# LEDBAKL_AP3036.net
KiCad netlist of a schematic drawn in Altium Designer
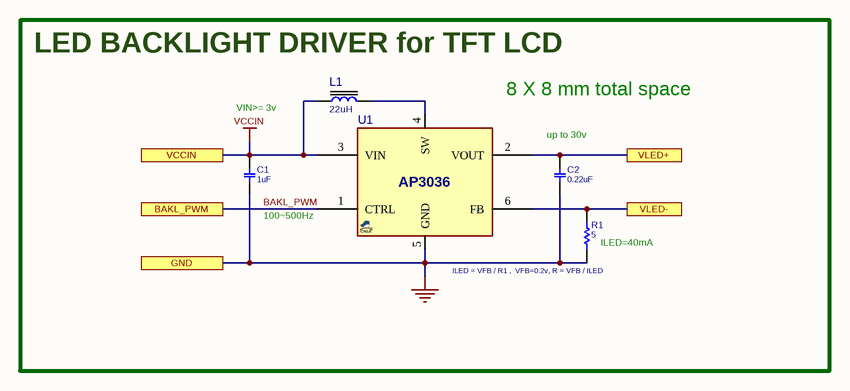
[diagram p0: LEDBAKL_AP3036.SchDoc]

(export (version "E")
  (design (tool "Eeschema 10.0.6"))
  (components
    (comp (ref "C1")
      (value "1uF")
      (footprint "C0603")
      (description "CAP, MLCC")
      (fields (field (name "MANF_P#") "CL10A105KB8NNNC") (field (name "MANF") "Samsung"))
      (libsource (lib "passive_smd") (part "CAP_SMD_MLCC"))
    )
    (comp (ref "C2")
      (value "0.22uF")
      (footprint "C0402")
      (description "CAP, MLCC")
      (libsource (lib "passive_smd") (part "CAP_SMD_MLCC"))
    )
    (comp (ref "L1")
      (value "22uH")
      (footprint "L_4")
      (description "INDUCTOR, POWER, SMD")
      (fields (field (name "MANF_P#") "CY43-22UH"))
      (libsource (lib "passive") (part "INDPWR_SMD"))
    )
    (comp (ref "R1")
      (value "5")
      (footprint "R0402")
      (description "RESISTOR, SMD, 20K, 0402")
      (fields (field (name "MANF") "Yageo") (field (name "MANF_P#") "RK73H1ETTP2002F"))
      (libsource (lib "chila_passive") (part "RES_SMD"))
    )
    (comp (ref "U1")
      (value "AP3036")
      (footprint "SOT23_6")
      (description "REG, Switching, Boost, 0.55A, ADJ, 1MHz, SOT-23-6")
      (fields (field (name "MANF_P#") "AP3036K, AP3036BK") (field (name "MANF") "Diodes"))
      (libsource (lib "pwr_switching_boost") (part "VREG_AP3036_SOT23"))
    )
  )
  (nets
    (net (code "1") (name "/BAKL_PWM") (class "Default")
      (node (ref "U1") (pin "1") (pinfunction "CTRL_1") (pintype "passive"))
    )
    (net (code "2") (name "/VLED+") (class "Default")
      (node (ref "C2") (pin "2") (pinfunction "2_2") (pintype "passive"))
      (node (ref "U1") (pin "2") (pinfunction "VOUT_2") (pintype "passive"))
    )
    (net (code "3") (name "/VLED-") (class "Default")
      (node (ref "R1") (pin "1") (pinfunction "1_1") (pintype "passive"))
      (node (ref "U1") (pin "6") (pinfunction "FB_6") (pintype "passive"))
    )
    (net (code "4") (name "GND") (class "Default")
      (node (ref "C1") (pin "1") (pinfunction "1_1") (pintype "passive"))
      (node (ref "C2") (pin "1") (pinfunction "1_1") (pintype "passive"))
      (node (ref "R1") (pin "2") (pinfunction "2_2") (pintype "passive"))
      (node (ref "U1") (pin "5") (pinfunction "GND_5") (pintype "passive"))
    )
    (net (code "5") (name "Net-(U1-SW)") (class "Default")
      (node (ref "L1") (pin "2") (pinfunction "2_2") (pintype "passive"))
      (node (ref "U1") (pin "4") (pinfunction "SW_4") (pintype "passive"))
    )
    (net (code "6") (name "VCCIN") (class "Default")
      (node (ref "C1") (pin "2") (pinfunction "2_2") (pintype "passive"))
      (node (ref "L1") (pin "1") (pinfunction "1_1") (pintype "passive"))
      (node (ref "U1") (pin "3") (pinfunction "VIN_3") (pintype "passive"))
    )
  )
)
